# SCH_RemoteRFController_2024-03-30.net
KiCad netlist of a schematic drawn in EasyEDA
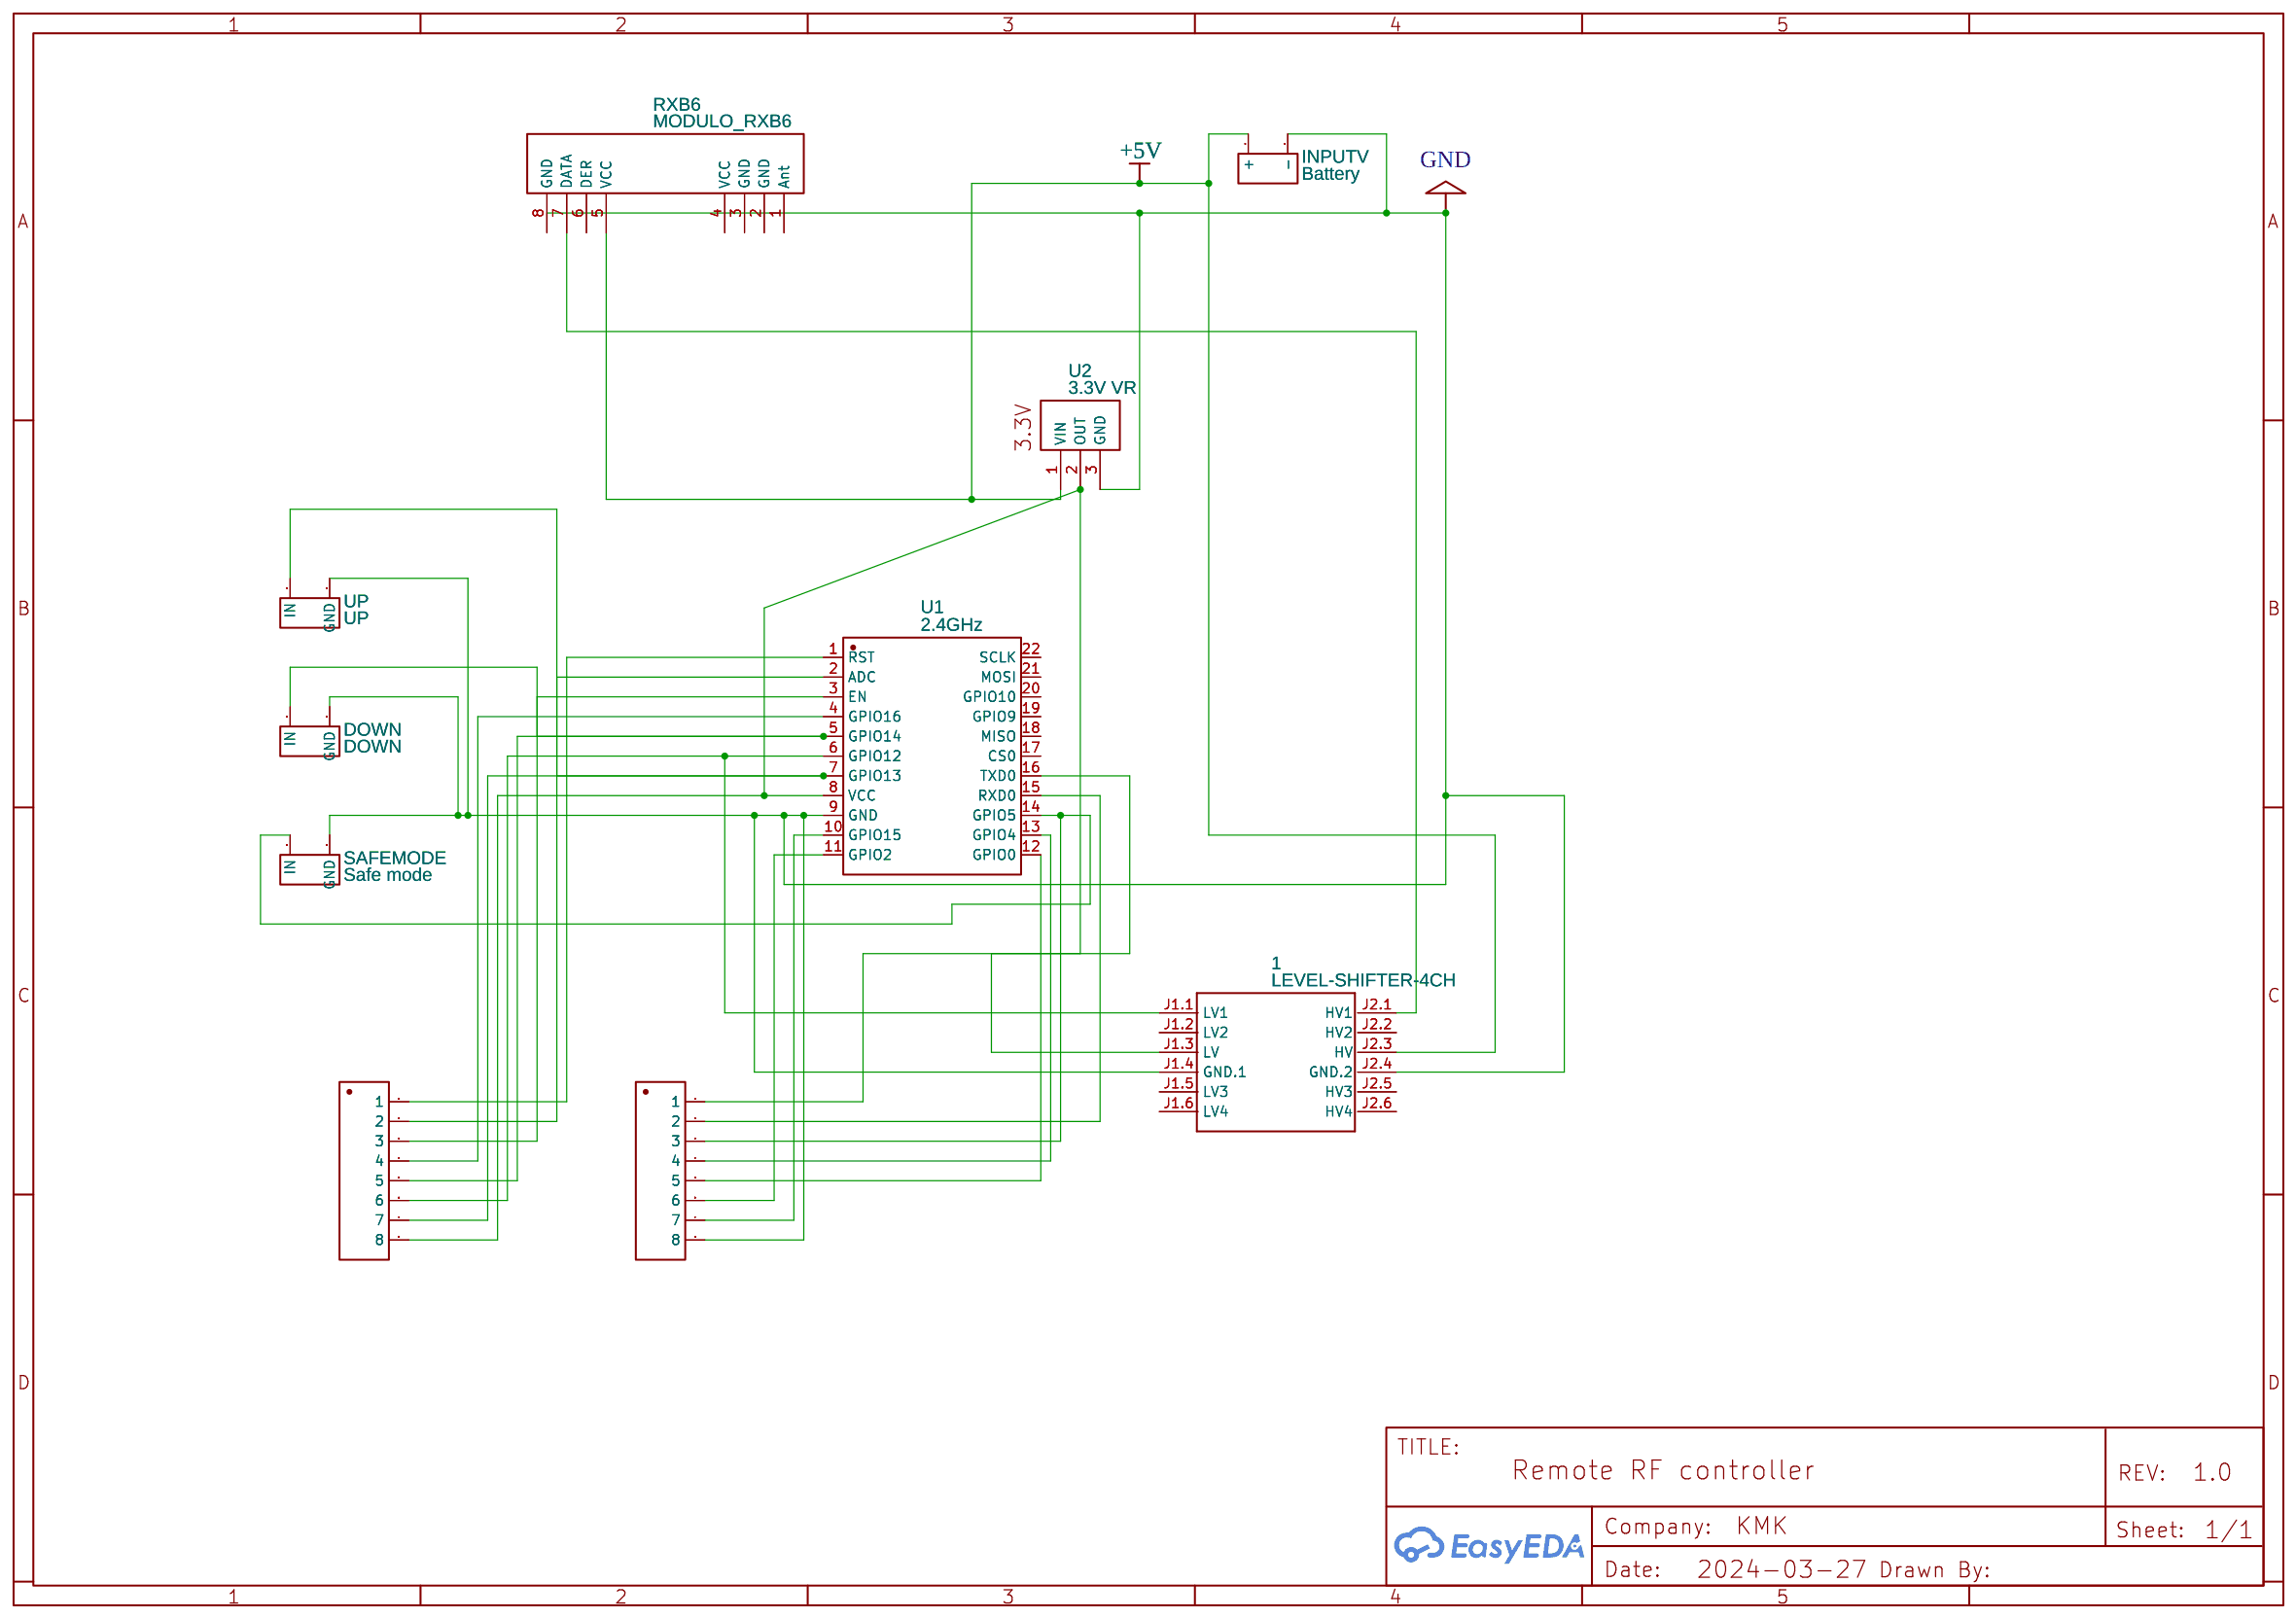
[diagram p0: schematic sheet]

(export (version "E")
  (design (tool "Eeschema 10.0.6"))
  (components
    (comp (ref "1") (value "LEVEL-SHIFTER-4CH") (libsource (lib "") (part "LEVEL-SHIFTER-4CH")))
    (comp (ref "DOWN")
      (value "DOWN")
      (fields
        (field (name "Manufacturer Part") "Female headerHDR1X8-2.54")
        (field (name "Manufacturer") "BOOMELE")
      )
      (libsource (lib "") (part "HEADER PAD 2X_2"))
    )
    (comp (ref "INPUTV")
      (value "Battery")
      (fields
        (field (name "Manufacturer Part") "Female headerHDR1X8-2.54")
        (field (name "Manufacturer") "BOOMELE")
      )
      (libsource (lib "") (part "HEADER PAD 2X"))
    )
    (comp (ref "RXB6")
      (value "MODULO_RXB6")
      (fields (field (name "Manufacturer Part") "RXB6-315"))
      (libsource (lib "") (part "MODULO_RXB6"))
    )
    (comp (ref "SAFEMODE")
      (value "Safe mode")
      (fields
        (field (name "Manufacturer Part") "Female headerHDR1X8-2.54")
        (field (name "Manufacturer") "BOOMELE")
      )
      (libsource (lib "") (part "HEADER PAD 2X_1"))
    )
    (comp (ref "ST7C1") (value "HEADER 1X8 Socket") (libsource (lib "") (part "HEADER 1X8 COPY")))
    (comp (ref "ST7C2") (value "HEADER 1X8 Socket") (libsource (lib "") (part "HEADER 1X8 COPY")))
    (comp (ref "U1")
      (value "2.4GHz")
      (fields
        (field (name "Manufacturer Part") "ESP-12F(ESP8266MOD)")
        (field (name "Manufacturer") "Ai-Thinker(安信可)")
      )
      (libsource (lib "") (part "ESP-12F(ESP8266MOD)"))
    )
    (comp (ref "U2") (value "3.3V VR") (libsource (lib "") (part "3.3V VR")))
    (comp (ref "UP")
      (value "UP")
      (fields
        (field (name "Manufacturer Part") "Female headerHDR1X8-2.54")
        (field (name "Manufacturer") "BOOMELE")
      )
      (libsource (lib "") (part "HEADER PAD 2X_3"))
    )
  )
  (nets
    (net (code "1") (name "+5V") (class "Default")
      (node (ref "1") (pin "J2.3") (pinfunction "HV_J2.3") (pintype "bidirectional"))
      (node (ref "INPUTV") (pin "2") (pinfunction "+_2") (pintype "unspecified"))
      (node (ref "RXB6") (pin "5") (pinfunction "VCC_5") (pintype "passive"))
      (node (ref "U2") (pin "1") (pinfunction "VIN_1") (pintype "unspecified"))
    )
    (net (code "2") (name "GND") (class "Default")
      (node (ref "1") (pin "J1.4") (pinfunction "GND.1_J1.4") (pintype "bidirectional"))
      (node (ref "1") (pin "J2.4") (pinfunction "GND.2_J2.4") (pintype "bidirectional"))
      (node (ref "DOWN") (pin "1") (pinfunction "GND_1") (pintype "unspecified"))
      (node (ref "INPUTV") (pin "1") (pinfunction "-_1") (pintype "unspecified"))
      (node (ref "RXB6") (pin "8") (pinfunction "GND_8") (pintype "passive"))
      (node (ref "SAFEMODE") (pin "1") (pinfunction "GND_1") (pintype "unspecified"))
      (node (ref "ST7C2") (pin "8") (pinfunction "8_8") (pintype "unspecified"))
      (node (ref "U1") (pin "9") (pinfunction "GND_9") (pintype "unspecified"))
      (node (ref "U2") (pin "3") (pinfunction "GND_3") (pintype "unspecified"))
      (node (ref "UP") (pin "1") (pinfunction "GND_1") (pintype "unspecified"))
    )
    (net (code "3") (name "Net-(1-HV1)") (class "Default")
      (node (ref "1") (pin "J2.1") (pinfunction "HV1_J2.1") (pintype "bidirectional"))
      (node (ref "RXB6") (pin "7") (pinfunction "DATA_7") (pintype "bidirectional"))
    )
    (net (code "4") (name "Net-(1-LV)") (class "Default")
      (node (ref "1") (pin "J1.3") (pinfunction "LV_J1.3") (pintype "bidirectional"))
      (node (ref "ST7C1") (pin "8") (pinfunction "8_8") (pintype "unspecified"))
      (node (ref "U1") (pin "8") (pinfunction "VCC_8") (pintype "unspecified"))
      (node (ref "U2") (pin "2") (pinfunction "OUT_2") (pintype "unspecified"))
    )
    (net (code "5") (name "Net-(1-LV1)") (class "Default")
      (node (ref "1") (pin "J1.1") (pinfunction "LV1_J1.1") (pintype "bidirectional"))
      (node (ref "ST7C1") (pin "6") (pinfunction "6_6") (pintype "unspecified"))
      (node (ref "U1") (pin "6") (pinfunction "GPIO12_6") (pintype "unspecified"))
    )
    (net (code "6") (name "Net-(DOWN-IN)") (class "Default")
      (node (ref "DOWN") (pin "2") (pinfunction "IN_2") (pintype "unspecified"))
      (node (ref "ST7C1") (pin "5") (pinfunction "5_5") (pintype "unspecified"))
      (node (ref "U1") (pin "5") (pinfunction "GPIO14_5") (pintype "unspecified"))
    )
    (net (code "7") (name "Net-(SAFEMODE-IN)") (class "Default")
      (node (ref "SAFEMODE") (pin "2") (pinfunction "IN_2") (pintype "unspecified"))
      (node (ref "ST7C2") (pin "3") (pinfunction "3_3") (pintype "unspecified"))
      (node (ref "U1") (pin "14") (pinfunction "GPIO5_14") (pintype "unspecified"))
    )
    (net (code "8") (name "Net-(U1-ADC)") (class "Default")
      (node (ref "ST7C1") (pin "2") (pinfunction "2_2") (pintype "unspecified"))
      (node (ref "U1") (pin "2") (pinfunction "ADC_2") (pintype "unspecified"))
    )
    (net (code "9") (name "Net-(U1-EN)") (class "Default")
      (node (ref "ST7C1") (pin "3") (pinfunction "3_3") (pintype "unspecified"))
      (node (ref "U1") (pin "3") (pinfunction "EN_3") (pintype "unspecified"))
    )
    (net (code "10") (name "Net-(U1-GPIO0)") (class "Default")
      (node (ref "ST7C2") (pin "5") (pinfunction "5_5") (pintype "unspecified"))
      (node (ref "U1") (pin "12") (pinfunction "GPIO0_12") (pintype "unspecified"))
    )
    (net (code "11") (name "Net-(U1-GPIO2)") (class "Default")
      (node (ref "ST7C2") (pin "6") (pinfunction "6_6") (pintype "unspecified"))
      (node (ref "U1") (pin "11") (pinfunction "GPIO2_11") (pintype "unspecified"))
    )
    (net (code "12") (name "Net-(U1-GPIO4)") (class "Default")
      (node (ref "ST7C2") (pin "4") (pinfunction "4_4") (pintype "unspecified"))
      (node (ref "U1") (pin "13") (pinfunction "GPIO4_13") (pintype "unspecified"))
    )
    (net (code "13") (name "Net-(U1-GPIO13)") (class "Default")
      (node (ref "ST7C1") (pin "7") (pinfunction "7_7") (pintype "unspecified"))
      (node (ref "U1") (pin "7") (pinfunction "GPIO13_7") (pintype "unspecified"))
      (node (ref "UP") (pin "2") (pinfunction "IN_2") (pintype "unspecified"))
    )
    (net (code "14") (name "Net-(U1-GPIO15)") (class "Default")
      (node (ref "ST7C2") (pin "7") (pinfunction "7_7") (pintype "unspecified"))
      (node (ref "U1") (pin "10") (pinfunction "GPIO15_10") (pintype "unspecified"))
    )
    (net (code "15") (name "Net-(U1-GPIO16)") (class "Default")
      (node (ref "ST7C1") (pin "4") (pinfunction "4_4") (pintype "unspecified"))
      (node (ref "U1") (pin "4") (pinfunction "GPIO16_4") (pintype "unspecified"))
    )
    (net (code "16") (name "Net-(U1-RST)") (class "Default")
      (node (ref "ST7C1") (pin "1") (pinfunction "1_1") (pintype "unspecified"))
      (node (ref "U1") (pin "1") (pinfunction "RST_1") (pintype "unspecified"))
    )
    (net (code "17") (name "Net-(U1-RXD0)") (class "Default")
      (node (ref "ST7C2") (pin "2") (pinfunction "2_2") (pintype "unspecified"))
      (node (ref "U1") (pin "15") (pinfunction "RXD0_15") (pintype "unspecified"))
    )
    (net (code "18") (name "Net-(U1-TXD0)") (class "Default")
      (node (ref "ST7C2") (pin "1") (pinfunction "1_1") (pintype "unspecified"))
      (node (ref "U1") (pin "16") (pinfunction "TXD0_16") (pintype "unspecified"))
    )
    (net (code "19") (name "unconnected-(1-HV2-PadJ2.2)") (class "Default")
      (node (ref "1") (pin "J2.2") (pinfunction "HV2_J2.2") (pintype "bidirectional"))
    )
    (net (code "20") (name "unconnected-(1-HV3-PadJ2.5)") (class "Default")
      (node (ref "1") (pin "J2.5") (pinfunction "HV3_J2.5") (pintype "bidirectional"))
    )
    (net (code "21") (name "unconnected-(1-HV4-PadJ2.6)") (class "Default")
      (node (ref "1") (pin "J2.6") (pinfunction "HV4_J2.6") (pintype "bidirectional"))
    )
    (net (code "22") (name "unconnected-(1-LV2-PadJ1.2)") (class "Default")
      (node (ref "1") (pin "J1.2") (pinfunction "LV2_J1.2") (pintype "bidirectional"))
    )
    (net (code "23") (name "unconnected-(1-LV3-PadJ1.5)") (class "Default")
      (node (ref "1") (pin "J1.5") (pinfunction "LV3_J1.5") (pintype "bidirectional"))
    )
    (net (code "24") (name "unconnected-(1-LV4-PadJ1.6)") (class "Default")
      (node (ref "1") (pin "J1.6") (pinfunction "LV4_J1.6") (pintype "bidirectional"))
    )
    (net (code "25") (name "unconnected-(RXB6-Ant-Pad1)") (class "Default")
      (node (ref "RXB6") (pin "1") (pinfunction "Ant_1") (pintype "bidirectional"))
    )
    (net (code "26") (name "unconnected-(RXB6-DER-Pad6)") (class "Default")
      (node (ref "RXB6") (pin "6") (pinfunction "DER_6") (pintype "bidirectional"))
    )
    (net (code "27") (name "unconnected-(RXB6-GND-Pad2)") (class "Default")
      (node (ref "RXB6") (pin "2") (pinfunction "GND_2") (pintype "passive"))
    )
    (net (code "28") (name "unconnected-(RXB6-GND-Pad3)") (class "Default")
      (node (ref "RXB6") (pin "3") (pinfunction "GND_3") (pintype "passive"))
    )
    (net (code "29") (name "unconnected-(RXB6-VCC-Pad4)") (class "Default")
      (node (ref "RXB6") (pin "4") (pinfunction "VCC_4") (pintype "passive"))
    )
    (net (code "30") (name "unconnected-(U1-CS0-Pad17)") (class "Default")
      (node (ref "U1") (pin "17") (pinfunction "CS0_17") (pintype "unspecified"))
    )
    (net (code "31") (name "unconnected-(U1-GPIO9-Pad19)") (class "Default")
      (node (ref "U1") (pin "19") (pinfunction "GPIO9_19") (pintype "unspecified"))
    )
    (net (code "32") (name "unconnected-(U1-GPIO10-Pad20)") (class "Default")
      (node (ref "U1") (pin "20") (pinfunction "GPIO10_20") (pintype "unspecified"))
    )
    (net (code "33") (name "unconnected-(U1-MISO-Pad18)") (class "Default")
      (node (ref "U1") (pin "18") (pinfunction "MISO_18") (pintype "unspecified"))
    )
    (net (code "34") (name "unconnected-(U1-MOSI-Pad21)") (class "Default")
      (node (ref "U1") (pin "21") (pinfunction "MOSI_21") (pintype "unspecified"))
    )
    (net (code "35") (name "unconnected-(U1-SCLK-Pad22)") (class "Default")
      (node (ref "U1") (pin "22") (pinfunction "SCLK_22") (pintype "unspecified"))
    )
  )
)
